# Sound_Card.net
KiCad netlist of a schematic drawn in Altium Designer
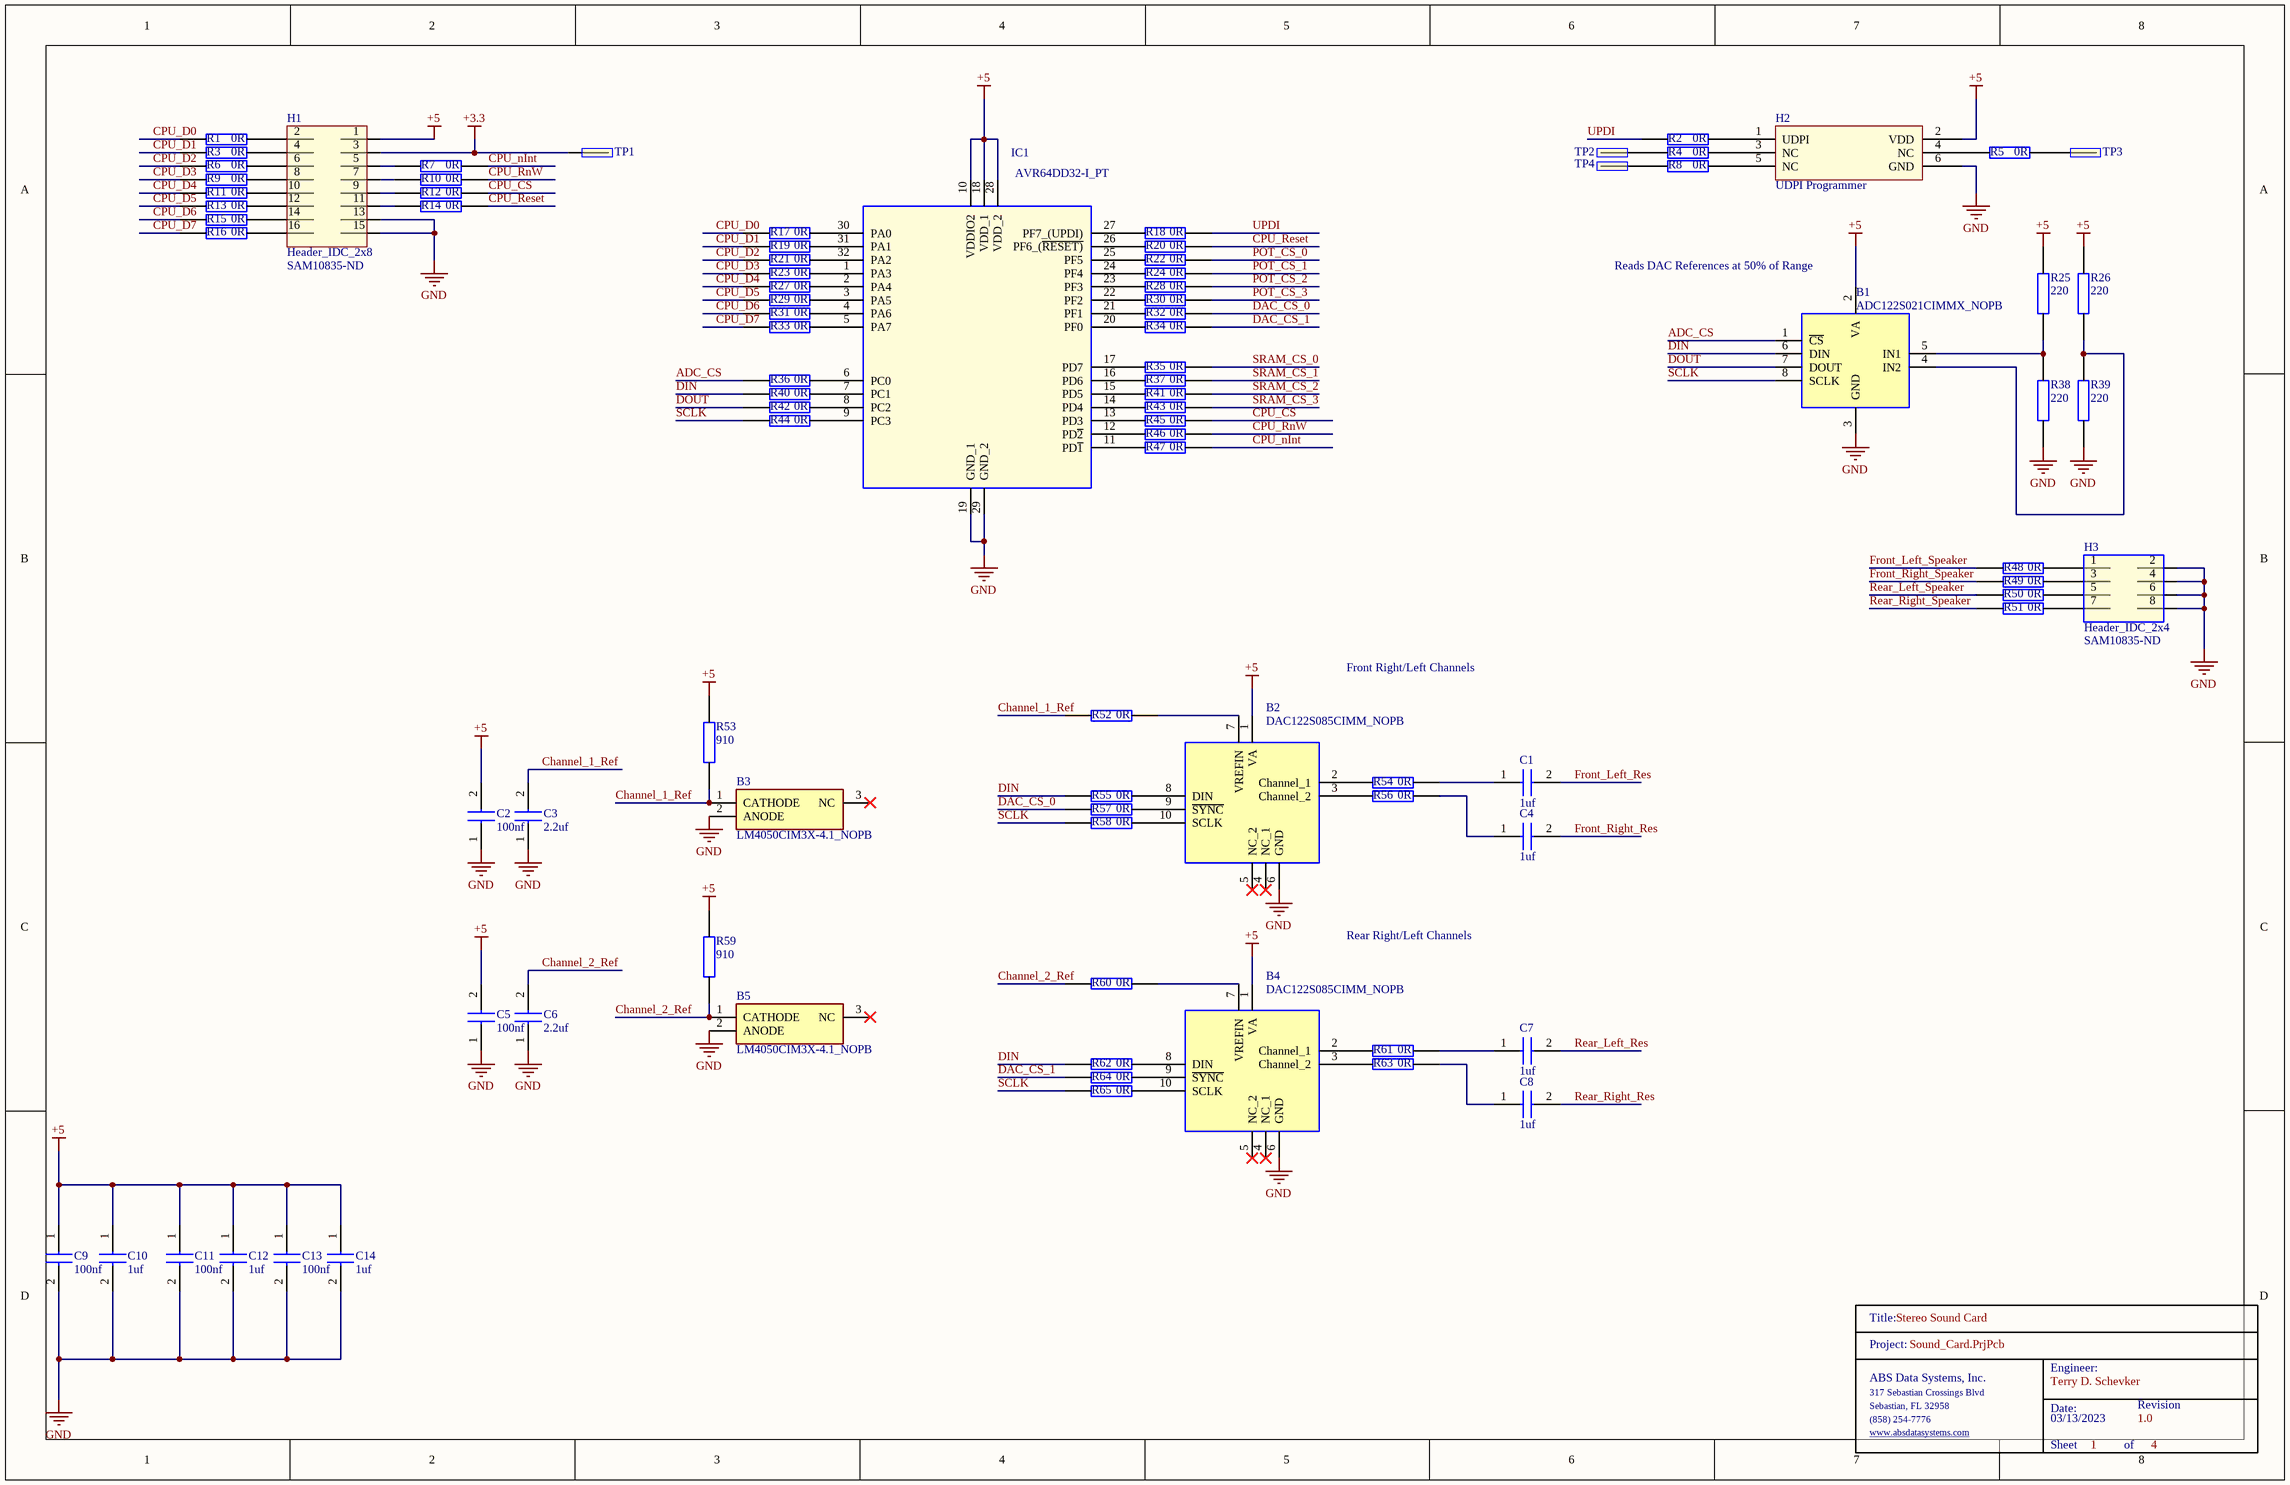
[diagram p0: Sound_Card.SchDoc]

(export (version "E")
  (design (tool "Eeschema 10.0.6"))
  (components
    (comp (ref "B1")
      (value "ADC122S021CIMMX_NOPB")
      (footprint "SOP65P490X110-8N")
      (description "2 Channel, 50 ksps to 200 ksps 12-Bit A/D Converter")
      (fields
        (field (name "MOUSER PART NUMBER") "926-A122S021CIMMXNPB")
        (field (name "MANUFACTURER_PART_NUMBER") "ADC122S021CIMMX/NOPB")
      )
      (libsource (lib "SemiConductors") (part "ADC122S021CIMMX_NOPB"))
    )
    (comp (ref "B2")
      (value "DAC122S085CIMM_NOPB")
      (footprint "SOP50P490X110-10N")
      (description "12-Bit Micro Power DUAL Digital-to-Analog Converter with Rail-to-Rail Output")
      (fields
        (field (name "MOUSER PART NUMBER") "926-DAC122S085CIMMNO")
        (field (name "MANUFACTURER_PART_NUMBER") "DAC122S085CIMM/NOPB")
      )
      (libsource (lib "SemiConductors") (part "DAC122S085CIMM_NOPB"))
    )
    (comp (ref "B3")
      (value "LM4050CIM3X-4.1_NOPB")
      (footprint "SOT95P237X95-3N")
      (description "50ppm/C Precision Micropower Shunt Voltage Reference")
      (fields
        (field (name "MOUSER PART NUMBER") "926-LM4050CIM3X41NPB")
        (field (name "MANUFACTURER_PART_NUMBER") "LM4050CIM3X-4.1/NOPB")
      )
      (libsource (lib "SemiConductors") (part "LM4050CIM3X-4.1_NOPB"))
    )
    (comp (ref "B4")
      (value "DAC122S085CIMM_NOPB")
      (footprint "SOP50P490X110-10N")
      (description "12-Bit Micro Power DUAL Digital-to-Analog Converter with Rail-to-Rail Output")
      (fields
        (field (name "MOUSER PART NUMBER") "926-DAC122S085CIMMNO")
        (field (name "MANUFACTURER_PART_NUMBER") "DAC122S085CIMM/NOPB")
      )
      (libsource (lib "SemiConductors") (part "DAC122S085CIMM_NOPB"))
    )
    (comp (ref "B5")
      (value "LM4050CIM3X-4.1_NOPB")
      (footprint "SOT95P237X95-3N")
      (description "50ppm/C Precision Micropower Shunt Voltage Reference")
      (fields
        (field (name "MOUSER PART NUMBER") "926-LM4050CIM3X41NPB")
        (field (name "MANUFACTURER_PART_NUMBER") "LM4050CIM3X-4.1/NOPB")
      )
      (libsource (lib "SemiConductors") (part "LM4050CIM3X-4.1_NOPB"))
    )
    (comp (ref "C1")
      (value "1uf")
      (footprint "0603")
      (description "Samsung Electro-Mechanics 0603 1uf")
      (libsource (lib "Capacitors") (part "CL10B105KA8NNNL"))
    )
    (comp (ref "C2")
      (value "100nf")
      (footprint "0603")
      (description "Samsung Electro-Mechanics 0603 100nf")
      (libsource (lib "Capacitors") (part "CL10B104JB8NNNC"))
    )
    (comp (ref "C3")
      (value "2.2uf")
      (footprint "0603")
      (description "Samsung Electro-Mechanics 0603 2.2uf")
      (libsource (lib "Capacitors") (part "CL10B225KP8NNNC"))
    )
    (comp (ref "C4")
      (value "1uf")
      (footprint "0603")
      (description "Samsung Electro-Mechanics 0603 1uf")
      (libsource (lib "Capacitors") (part "CL10B105KA8NNNL"))
    )
    (comp (ref "C5")
      (value "100nf")
      (footprint "0603")
      (description "Samsung Electro-Mechanics 0603 100nf")
      (libsource (lib "Capacitors") (part "CL10B104JB8NNNC"))
    )
    (comp (ref "C6")
      (value "2.2uf")
      (footprint "0603")
      (description "Samsung Electro-Mechanics 0603 2.2uf")
      (libsource (lib "Capacitors") (part "CL10B225KP8NNNC"))
    )
    (comp (ref "C7")
      (value "1uf")
      (footprint "0603")
      (description "Samsung Electro-Mechanics 0603 1uf")
      (libsource (lib "Capacitors") (part "CL10B105KA8NNNL"))
    )
    (comp (ref "C8")
      (value "1uf")
      (footprint "0603")
      (description "Samsung Electro-Mechanics 0603 1uf")
      (libsource (lib "Capacitors") (part "CL10B105KA8NNNL"))
    )
    (comp (ref "C9")
      (value "100nf")
      (footprint "0603")
      (description "Samsung Electro-Mechanics 0603 100nf")
      (libsource (lib "Capacitors") (part "CL10B104JB8NNNC"))
    )
    (comp (ref "C10")
      (value "1uf")
      (footprint "0603")
      (description "Samsung Electro-Mechanics 0603 1uf")
      (libsource (lib "Capacitors") (part "CL10B105KA8NNNL"))
    )
    (comp (ref "C11")
      (value "100nf")
      (footprint "0603")
      (description "Samsung Electro-Mechanics 0603 100nf")
      (libsource (lib "Capacitors") (part "CL10B104JB8NNNC"))
    )
    (comp (ref "C12")
      (value "1uf")
      (footprint "0603")
      (description "Samsung Electro-Mechanics 0603 1uf")
      (libsource (lib "Capacitors") (part "CL10B105KA8NNNL"))
    )
    (comp (ref "C13")
      (value "100nf")
      (footprint "0603")
      (description "Samsung Electro-Mechanics 0603 100nf")
      (libsource (lib "Capacitors") (part "CL10B104JB8NNNC"))
    )
    (comp (ref "C14")
      (value "1uf")
      (footprint "0603")
      (description "Samsung Electro-Mechanics 0603 1uf")
      (libsource (lib "Capacitors") (part "CL10B105KA8NNNL"))
    )
    (comp (ref "H1")
      (value "Header_IDC_2x8")
      (footprint "HEADER16")
      (description "16 Pin 2x8 Through Hold IDC Connector")
      (fields
        (field (name "MANUFACTURER") "Samtec")
        (field (name "MANUFACTURER PART NUMBER") "TST-108-01-G-D")
        (field (name "SUPPLIER PART NUMBER 1") "SAM10835-ND")
      )
      (libsource (lib "Misc") (part "Header_IDC_2x8"))
    )
    (comp (ref "H2")
      (value "UDPI Programmer")
      (footprint "HDR2X3")
      (description "6 Pin 2X3 Through Hole Header")
      (libsource (lib "Misc") (part "UDPI Programmer"))
    )
    (comp (ref "H3")
      (value "Header_IDC_2x4")
      (footprint "HDR2X4")
      (description "8 Pin 2x4 Through Hold IDC Connector")
      (fields
        (field (name "MANUFACTURER") "Samtec")
        (field (name "MANUFACTURER PART NUMBER") "TST-105-01-G-D")
        (field (name "SUPPLIER PART NUMBER 1") "SAM10835-ND")
      )
      (libsource (lib "Misc") (part "Header_IDC_2x4"))
    )
    (comp (ref "IC1")
      (value "AVR64DD32-I_PT")
      (footprint "QFP80P900X900X120-32N")
      (description "Integrated Circuit")
      (fields (field (name "MANUFACTURER_PART_NUMBER") "AVR64DD32-I/PT ¦ MULTI-VOLTAGE I/O"))
      (libsource (lib "CPU_Memory") (part "AVR64DD32-I_PT"))
    )
    (comp (ref "R1")
      (value "0R")
      (footprint "0603")
      (description "YAGEO 0603 0 ohm")
      (fields
        (field (name "MOUSER PART NUMBER") "603-RC0603JR-070RL")
        (field (name "MANUFACTURER_PART_NUMBER") "RC0603JR-070RL")
      )
      (libsource (lib "Resistors") (part "RC0603JR-070RL"))
    )
    (comp (ref "R2")
      (value "0R")
      (footprint "0603")
      (description "YAGEO 0603 0 ohm")
      (fields
        (field (name "MOUSER PART NUMBER") "603-RC0603JR-070RL")
        (field (name "MANUFACTURER_PART_NUMBER") "RC0603JR-070RL")
      )
      (libsource (lib "Resistors") (part "RC0603JR-070RL"))
    )
    (comp (ref "R3")
      (value "0R")
      (footprint "0603")
      (description "YAGEO 0603 0 ohm")
      (fields
        (field (name "MOUSER PART NUMBER") "603-RC0603JR-070RL")
        (field (name "MANUFACTURER_PART_NUMBER") "RC0603JR-070RL")
      )
      (libsource (lib "Resistors") (part "RC0603JR-070RL"))
    )
    (comp (ref "R4")
      (value "0R")
      (footprint "0603")
      (description "YAGEO 0603 0 ohm")
      (fields
        (field (name "MOUSER PART NUMBER") "603-RC0603JR-070RL")
        (field (name "MANUFACTURER_PART_NUMBER") "RC0603JR-070RL")
      )
      (libsource (lib "Resistors") (part "RC0603JR-070RL"))
    )
    (comp (ref "R5")
      (value "0R")
      (footprint "0603")
      (description "YAGEO 0603 0 ohm")
      (fields
        (field (name "MOUSER PART NUMBER") "603-RC0603JR-070RL")
        (field (name "MANUFACTURER_PART_NUMBER") "RC0603JR-070RL")
      )
      (libsource (lib "Resistors") (part "RC0603JR-070RL"))
    )
    (comp (ref "R6")
      (value "0R")
      (footprint "0603")
      (description "YAGEO 0603 0 ohm")
      (fields
        (field (name "MOUSER PART NUMBER") "603-RC0603JR-070RL")
        (field (name "MANUFACTURER_PART_NUMBER") "RC0603JR-070RL")
      )
      (libsource (lib "Resistors") (part "RC0603JR-070RL"))
    )
    (comp (ref "R7")
      (value "0R")
      (footprint "0603")
      (description "YAGEO 0603 0 ohm")
      (fields
        (field (name "MOUSER PART NUMBER") "603-RC0603JR-070RL")
        (field (name "MANUFACTURER_PART_NUMBER") "RC0603JR-070RL")
      )
      (libsource (lib "Resistors") (part "RC0603JR-070RL"))
    )
    (comp (ref "R8")
      (value "0R")
      (footprint "0603")
      (description "YAGEO 0603 0 ohm")
      (fields
        (field (name "MOUSER PART NUMBER") "603-RC0603JR-070RL")
        (field (name "MANUFACTURER_PART_NUMBER") "RC0603JR-070RL")
      )
      (libsource (lib "Resistors") (part "RC0603JR-070RL"))
    )
    (comp (ref "R9")
      (value "0R")
      (footprint "0603")
      (description "YAGEO 0603 0 ohm")
      (fields
        (field (name "MOUSER PART NUMBER") "603-RC0603JR-070RL")
        (field (name "MANUFACTURER_PART_NUMBER") "RC0603JR-070RL")
      )
      (libsource (lib "Resistors") (part "RC0603JR-070RL"))
    )
    (comp (ref "R10")
      (value "0R")
      (footprint "0603")
      (description "YAGEO 0603 0 ohm")
      (fields
        (field (name "MOUSER PART NUMBER") "603-RC0603JR-070RL")
        (field (name "MANUFACTURER_PART_NUMBER") "RC0603JR-070RL")
      )
      (libsource (lib "Resistors") (part "RC0603JR-070RL"))
    )
    (comp (ref "R11")
      (value "0R")
      (footprint "0603")
      (description "YAGEO 0603 0 ohm")
      (fields
        (field (name "MOUSER PART NUMBER") "603-RC0603JR-070RL")
        (field (name "MANUFACTURER_PART_NUMBER") "RC0603JR-070RL")
      )
      (libsource (lib "Resistors") (part "RC0603JR-070RL"))
    )
    (comp (ref "R12")
      (value "0R")
      (footprint "0603")
      (description "YAGEO 0603 0 ohm")
      (fields
        (field (name "MOUSER PART NUMBER") "603-RC0603JR-070RL")
        (field (name "MANUFACTURER_PART_NUMBER") "RC0603JR-070RL")
      )
      (libsource (lib "Resistors") (part "RC0603JR-070RL"))
    )
    (comp (ref "R13")
      (value "0R")
      (footprint "0603")
      (description "YAGEO 0603 0 ohm")
      (fields
        (field (name "MOUSER PART NUMBER") "603-RC0603JR-070RL")
        (field (name "MANUFACTURER_PART_NUMBER") "RC0603JR-070RL")
      )
      (libsource (lib "Resistors") (part "RC0603JR-070RL"))
    )
    (comp (ref "R14")
      (value "0R")
      (footprint "0603")
      (description "YAGEO 0603 0 ohm")
      (fields
        (field (name "MOUSER PART NUMBER") "603-RC0603JR-070RL")
        (field (name "MANUFACTURER_PART_NUMBER") "RC0603JR-070RL")
      )
      (libsource (lib "Resistors") (part "RC0603JR-070RL"))
    )
    (comp (ref "R15")
      (value "0R")
      (footprint "0603")
      (description "YAGEO 0603 0 ohm")
      (fields
        (field (name "MOUSER PART NUMBER") "603-RC0603JR-070RL")
        (field (name "MANUFACTURER_PART_NUMBER") "RC0603JR-070RL")
      )
      (libsource (lib "Resistors") (part "RC0603JR-070RL"))
    )
    (comp (ref "R16")
      (value "0R")
      (footprint "0603")
      (description "YAGEO 0603 0 ohm")
      (fields
        (field (name "MOUSER PART NUMBER") "603-RC0603JR-070RL")
        (field (name "MANUFACTURER_PART_NUMBER") "RC0603JR-070RL")
      )
      (libsource (lib "Resistors") (part "RC0603JR-070RL"))
    )
    (comp (ref "R17")
      (value "0R")
      (footprint "0603")
      (description "YAGEO 0603 0 ohm")
      (fields
        (field (name "MOUSER PART NUMBER") "603-RC0603JR-070RL")
        (field (name "MANUFACTURER_PART_NUMBER") "RC0603JR-070RL")
      )
      (libsource (lib "Resistors") (part "RC0603JR-070RL"))
    )
    (comp (ref "R18")
      (value "0R")
      (footprint "0603")
      (description "YAGEO 0603 0 ohm")
      (fields
        (field (name "MOUSER PART NUMBER") "603-RC0603JR-070RL")
        (field (name "MANUFACTURER_PART_NUMBER") "RC0603JR-070RL")
      )
      (libsource (lib "Resistors") (part "RC0603JR-070RL"))
    )
    (comp (ref "R19")
      (value "0R")
      (footprint "0603")
      (description "YAGEO 0603 0 ohm")
      (fields
        (field (name "MOUSER PART NUMBER") "603-RC0603JR-070RL")
        (field (name "MANUFACTURER_PART_NUMBER") "RC0603JR-070RL")
      )
      (libsource (lib "Resistors") (part "RC0603JR-070RL"))
    )
    (comp (ref "R20")
      (value "0R")
      (footprint "0603")
      (description "YAGEO 0603 0 ohm")
      (fields
        (field (name "MOUSER PART NUMBER") "603-RC0603JR-070RL")
        (field (name "MANUFACTURER_PART_NUMBER") "RC0603JR-070RL")
      )
      (libsource (lib "Resistors") (part "RC0603JR-070RL"))
    )
    (comp (ref "R21")
      (value "0R")
      (footprint "0603")
      (description "YAGEO 0603 0 ohm")
      (fields
        (field (name "MOUSER PART NUMBER") "603-RC0603JR-070RL")
        (field (name "MANUFACTURER_PART_NUMBER") "RC0603JR-070RL")
      )
      (libsource (lib "Resistors") (part "RC0603JR-070RL"))
    )
    (comp (ref "R22")
      (value "0R")
      (footprint "0603")
      (description "YAGEO 0603 0 ohm")
      (fields
        (field (name "MOUSER PART NUMBER") "603-RC0603JR-070RL")
        (field (name "MANUFACTURER_PART_NUMBER") "RC0603JR-070RL")
      )
      (libsource (lib "Resistors") (part "RC0603JR-070RL"))
    )
    (comp (ref "R23")
      (value "0R")
      (footprint "0603")
      (description "YAGEO 0603 0 ohm")
      (fields
        (field (name "MOUSER PART NUMBER") "603-RC0603JR-070RL")
        (field (name "MANUFACTURER_PART_NUMBER") "RC0603JR-070RL")
      )
      (libsource (lib "Resistors") (part "RC0603JR-070RL"))
    )
    (comp (ref "R24")
      (value "0R")
      (footprint "0603")
      (description "YAGEO 0603 0 ohm")
      (fields
        (field (name "MOUSER PART NUMBER") "603-RC0603JR-070RL")
        (field (name "MANUFACTURER_PART_NUMBER") "RC0603JR-070RL")
      )
      (libsource (lib "Resistors") (part "RC0603JR-070RL"))
    )
    (comp (ref "R25")
      (value "220")
      (footprint "0603")
      (description "YAGEO 0603 220 ohm")
      (fields
        (field (name "MOUSER PART NUMBER") "603-RC0603JR-070RL")
        (field (name "MANUFACTURER_PART_NUMBER") "RC0603JR-070RL")
      )
      (libsource (lib "Resistors") (part "RC0603JR-07220RL"))
    )
    (comp (ref "R26")
      (value "220")
      (footprint "0603")
      (description "YAGEO 0603 220 ohm")
      (fields
        (field (name "MOUSER PART NUMBER") "603-RC0603JR-070RL")
        (field (name "MANUFACTURER_PART_NUMBER") "RC0603JR-070RL")
      )
      (libsource (lib "Resistors") (part "RC0603JR-07220RL"))
    )
    (comp (ref "R27")
      (value "0R")
      (footprint "0603")
      (description "YAGEO 0603 0 ohm")
      (fields
        (field (name "MOUSER PART NUMBER") "603-RC0603JR-070RL")
        (field (name "MANUFACTURER_PART_NUMBER") "RC0603JR-070RL")
      )
      (libsource (lib "Resistors") (part "RC0603JR-070RL"))
    )
    (comp (ref "R28")
      (value "0R")
      (footprint "0603")
      (description "YAGEO 0603 0 ohm")
      (fields
        (field (name "MOUSER PART NUMBER") "603-RC0603JR-070RL")
        (field (name "MANUFACTURER_PART_NUMBER") "RC0603JR-070RL")
      )
      (libsource (lib "Resistors") (part "RC0603JR-070RL"))
    )
    (comp (ref "R29")
      (value "0R")
      (footprint "0603")
      (description "YAGEO 0603 0 ohm")
      (fields
        (field (name "MOUSER PART NUMBER") "603-RC0603JR-070RL")
        (field (name "MANUFACTURER_PART_NUMBER") "RC0603JR-070RL")
      )
      (libsource (lib "Resistors") (part "RC0603JR-070RL"))
    )
    (comp (ref "R30")
      (value "0R")
      (footprint "0603")
      (description "YAGEO 0603 0 ohm")
      (fields
        (field (name "MOUSER PART NUMBER") "603-RC0603JR-070RL")
        (field (name "MANUFACTURER_PART_NUMBER") "RC0603JR-070RL")
      )
      (libsource (lib "Resistors") (part "RC0603JR-070RL"))
    )
    (comp (ref "R31")
      (value "0R")
      (footprint "0603")
      (description "YAGEO 0603 0 ohm")
      (fields
        (field (name "MOUSER PART NUMBER") "603-RC0603JR-070RL")
        (field (name "MANUFACTURER_PART_NUMBER") "RC0603JR-070RL")
      )
      (libsource (lib "Resistors") (part "RC0603JR-070RL"))
    )
    (comp (ref "R32")
      (value "0R")
      (footprint "0603")
      (description "YAGEO 0603 0 ohm")
      (fields
        (field (name "MOUSER PART NUMBER") "603-RC0603JR-070RL")
        (field (name "MANUFACTURER_PART_NUMBER") "RC0603JR-070RL")
      )
      (libsource (lib "Resistors") (part "RC0603JR-070RL"))
    )
    (comp (ref "R33")
      (value "0R")
      (footprint "0603")
      (description "YAGEO 0603 0 ohm")
      (fields
        (field (name "MOUSER PART NUMBER") "603-RC0603JR-070RL")
        (field (name "MANUFACTURER_PART_NUMBER") "RC0603JR-070RL")
      )
      (libsource (lib "Resistors") (part "RC0603JR-070RL"))
    )
    (comp (ref "R34")
      (value "0R")
      (footprint "0603")
      (description "YAGEO 0603 0 ohm")
      (fields
        (field (name "MOUSER PART NUMBER") "603-RC0603JR-070RL")
        (field (name "MANUFACTURER_PART_NUMBER") "RC0603JR-070RL")
      )
      (libsource (lib "Resistors") (part "RC0603JR-070RL"))
    )
    (comp (ref "R35")
      (value "0R")
      (footprint "0603")
      (description "YAGEO 0603 0 ohm")
      (fields
        (field (name "MOUSER PART NUMBER") "603-RC0603JR-070RL")
        (field (name "MANUFACTURER_PART_NUMBER") "RC0603JR-070RL")
      )
      (libsource (lib "Resistors") (part "RC0603JR-070RL"))
    )
    (comp (ref "R36")
      (value "0R")
      (footprint "0603")
      (description "YAGEO 0603 0 ohm")
      (fields
        (field (name "MOUSER PART NUMBER") "603-RC0603JR-070RL")
        (field (name "MANUFACTURER_PART_NUMBER") "RC0603JR-070RL")
      )
      (libsource (lib "Resistors") (part "RC0603JR-070RL"))
    )
    (comp (ref "R37")
      (value "0R")
      (footprint "0603")
      (description "YAGEO 0603 0 ohm")
      (fields
        (field (name "MOUSER PART NUMBER") "603-RC0603JR-070RL")
        (field (name "MANUFACTURER_PART_NUMBER") "RC0603JR-070RL")
      )
      (libsource (lib "Resistors") (part "RC0603JR-070RL"))
    )
    (comp (ref "R38")
      (value "220")
      (footprint "0603")
      (description "YAGEO 0603 220 ohm")
      (fields
        (field (name "MOUSER PART NUMBER") "603-RC0603JR-070RL")
        (field (name "MANUFACTURER_PART_NUMBER") "RC0603JR-070RL")
      )
      (libsource (lib "Resistors") (part "RC0603JR-07220RL"))
    )
    (comp (ref "R39")
      (value "220")
      (footprint "0603")
      (description "YAGEO 0603 220 ohm")
      (fields
        (field (name "MOUSER PART NUMBER") "603-RC0603JR-070RL")
        (field (name "MANUFACTURER_PART_NUMBER") "RC0603JR-070RL")
      )
      (libsource (lib "Resistors") (part "RC0603JR-07220RL"))
    )
    (comp (ref "R40")
      (value "0R")
      (footprint "0603")
      (description "YAGEO 0603 0 ohm")
      (fields
        (field (name "MOUSER PART NUMBER") "603-RC0603JR-070RL")
        (field (name "MANUFACTURER_PART_NUMBER") "RC0603JR-070RL")
      )
      (libsource (lib "Resistors") (part "RC0603JR-070RL"))
    )
    (comp (ref "R41")
      (value "0R")
      (footprint "0603")
      (description "YAGEO 0603 0 ohm")
      (fields
        (field (name "MOUSER PART NUMBER") "603-RC0603JR-070RL")
        (field (name "MANUFACTURER_PART_NUMBER") "RC0603JR-070RL")
      )
      (libsource (lib "Resistors") (part "RC0603JR-070RL"))
    )
    (comp (ref "R42")
      (value "0R")
      (footprint "0603")
      (description "YAGEO 0603 0 ohm")
      (fields
        (field (name "MOUSER PART NUMBER") "603-RC0603JR-070RL")
        (field (name "MANUFACTURER_PART_NUMBER") "RC0603JR-070RL")
      )
      (libsource (lib "Resistors") (part "RC0603JR-070RL"))
    )
    (comp (ref "R43")
      (value "0R")
      (footprint "0603")
      (description "YAGEO 0603 0 ohm")
      (fields
        (field (name "MOUSER PART NUMBER") "603-RC0603JR-070RL")
        (field (name "MANUFACTURER_PART_NUMBER") "RC0603JR-070RL")
      )
      (libsource (lib "Resistors") (part "RC0603JR-070RL"))
    )
    (comp (ref "R44")
      (value "0R")
      (footprint "0603")
      (description "YAGEO 0603 0 ohm")
      (fields
        (field (name "MOUSER PART NUMBER") "603-RC0603JR-070RL")
        (field (name "MANUFACTURER_PART_NUMBER") "RC0603JR-070RL")
      )
      (libsource (lib "Resistors") (part "RC0603JR-070RL"))
    )
    (comp (ref "R45")
      (value "0R")
      (footprint "0603")
      (description "YAGEO 0603 0 ohm")
      (fields
        (field (name "MOUSER PART NUMBER") "603-RC0603JR-070RL")
        (field (name "MANUFACTURER_PART_NUMBER") "RC0603JR-070RL")
      )
      (libsource (lib "Resistors") (part "RC0603JR-070RL"))
    )
    (comp (ref "R46")
      (value "0R")
      (footprint "0603")
      (description "YAGEO 0603 0 ohm")
      (fields
        (field (name "MOUSER PART NUMBER") "603-RC0603JR-070RL")
        (field (name "MANUFACTURER_PART_NUMBER") "RC0603JR-070RL")
      )
      (libsource (lib "Resistors") (part "RC0603JR-070RL"))
    )
    (comp (ref "R47")
      (value "0R")
      (footprint "0603")
      (description "YAGEO 0603 0 ohm")
      (fields
        (field (name "MOUSER PART NUMBER") "603-RC0603JR-070RL")
        (field (name "MANUFACTURER_PART_NUMBER") "RC0603JR-070RL")
      )
      (libsource (lib "Resistors") (part "RC0603JR-070RL"))
    )
    (comp (ref "R48")
      (value "0R")
      (footprint "0603")
      (description "YAGEO 0603 0 ohm")
      (fields
        (field (name "MOUSER PART NUMBER") "603-RC0603JR-070RL")
        (field (name "MANUFACTURER_PART_NUMBER") "RC0603JR-070RL")
      )
      (libsource (lib "Resistors") (part "RC0603JR-070RL"))
    )
    (comp (ref "R49")
      (value "0R")
      (footprint "0603")
      (description "YAGEO 0603 0 ohm")
      (fields
        (field (name "MOUSER PART NUMBER") "603-RC0603JR-070RL")
        (field (name "MANUFACTURER_PART_NUMBER") "RC0603JR-070RL")
      )
      (libsource (lib "Resistors") (part "RC0603JR-070RL"))
    )
    (comp (ref "R50")
      (value "0R")
      (footprint "0603")
      (description "YAGEO 0603 0 ohm")
      (fields
        (field (name "MOUSER PART NUMBER") "603-RC0603JR-070RL")
        (field (name "MANUFACTURER_PART_NUMBER") "RC0603JR-070RL")
      )
      (libsource (lib "Resistors") (part "RC0603JR-070RL"))
    )
    (comp (ref "R51")
      (value "0R")
      (footprint "0603")
      (description "YAGEO 0603 0 ohm")
      (fields
        (field (name "MOUSER PART NUMBER") "603-RC0603JR-070RL")
        (field (name "MANUFACTURER_PART_NUMBER") "RC0603JR-070RL")
      )
      (libsource (lib "Resistors") (part "RC0603JR-070RL"))
    )
    (comp (ref "R52")
      (value "0R")
      (footprint "0603")
      (description "YAGEO 0603 0 ohm")
      (fields
        (field (name "MOUSER PART NUMBER") "603-RC0603JR-070RL")
        (field (name "MANUFACTURER_PART_NUMBER") "RC0603JR-070RL")
      )
      (libsource (lib "Resistors") (part "RC0603JR-070RL"))
    )
    (comp (ref "R53")
      (value "910")
      (footprint "0603")
      (description "YAGEO 0603 910 ohm")
      (fields
        (field (name "MOUSER PART NUMBER") "603-RC0603JR-070RL")
        (field (name "MANUFACTURER_PART_NUMBER") "RC0603JR-070RL")
      )
      (libsource (lib "Resistors") (part "RT0603BRC07910RL"))
    )
    (comp (ref "R54")
      (value "0R")
      (footprint "0603")
      (description "YAGEO 0603 0 ohm")
      (fields
        (field (name "MOUSER PART NUMBER") "603-RC0603JR-070RL")
        (field (name "MANUFACTURER_PART_NUMBER") "RC0603JR-070RL")
      )
      (libsource (lib "Resistors") (part "RC0603JR-070RL"))
    )
    (comp (ref "R55")
      (value "0R")
      (footprint "0603")
      (description "YAGEO 0603 0 ohm")
      (fields
        (field (name "MOUSER PART NUMBER") "603-RC0603JR-070RL")
        (field (name "MANUFACTURER_PART_NUMBER") "RC0603JR-070RL")
      )
      (libsource (lib "Resistors") (part "RC0603JR-070RL"))
    )
    (comp (ref "R56")
      (value "0R")
      (footprint "0603")
      (description "YAGEO 0603 0 ohm")
      (fields
        (field (name "MOUSER PART NUMBER") "603-RC0603JR-070RL")
        (field (name "MANUFACTURER_PART_NUMBER") "RC0603JR-070RL")
      )
      (libsource (lib "Resistors") (part "RC0603JR-070RL"))
    )
    (comp (ref "R57")
      (value "0R")
      (footprint "0603")
      (description "YAGEO 0603 0 ohm")
      (fields
        (field (name "MOUSER PART NUMBER") "603-RC0603JR-070RL")
        (field (name "MANUFACTURER_PART_NUMBER") "RC0603JR-070RL")
      )
      (libsource (lib "Resistors") (part "RC0603JR-070RL"))
    )
    (comp (ref "R58")
      (value "0R")
      (footprint "0603")
      (description "YAGEO 0603 0 ohm")
      (fields
        (field (name "MOUSER PART NUMBER") "603-RC0603JR-070RL")
        (field (name "MANUFACTURER_PART_NUMBER") "RC0603JR-070RL")
      )
      (libsource (lib "Resistors") (part "RC0603JR-070RL"))
    )
    (comp (ref "R59")
      (value "910")
      (footprint "0603")
      (description "YAGEO 0603 910 ohm")
      (fields
        (field (name "MOUSER PART NUMBER") "603-RC0603JR-070RL")
        (field (name "MANUFACTURER_PART_NUMBER") "RC0603JR-070RL")
      )
      (libsource (lib "Resistors") (part "RT0603BRC07910RL"))
    )
    (comp (ref "R60")
      (value "0R")
      (footprint "0603")
      (description "YAGEO 0603 0 ohm")
      (fields
        (field (name "MOUSER PART NUMBER") "603-RC0603JR-070RL")
        (field (name "MANUFACTURER_PART_NUMBER") "RC0603JR-070RL")
      )
      (libsource (lib "Resistors") (part "RC0603JR-070RL"))
    )
    (comp (ref "R61")
      (value "0R")
      (footprint "0603")
      (description "YAGEO 0603 0 ohm")
      (fields
        (field (name "MOUSER PART NUMBER") "603-RC0603JR-070RL")
        (field (name "MANUFACTURER_PART_NUMBER") "RC0603JR-070RL")
      )
      (libsource (lib "Resistors") (part "RC0603JR-070RL"))
    )
    (comp (ref "R62")
      (value "0R")
      (footprint "0603")
      (description "YAGEO 0603 0 ohm")
      (fields
        (field (name "MOUSER PART NUMBER") "603-RC0603JR-070RL")
        (field (name "MANUFACTURER_PART_NUMBER") "RC0603JR-070RL")
      )
      (libsource (lib "Resistors") (part "RC0603JR-070RL"))
    )
    (comp (ref "R63")
      (value "0R")
      (footprint "0603")
      (description "YAGEO 0603 0 ohm")
      (fields
        (field (name "MOUSER PART NUMBER") "603-RC0603JR-070RL")
        (field (name "MANUFACTURER_PART_NUMBER") "RC0603JR-070RL")
      )
      (libsource (lib "Resistors") (part "RC0603JR-070RL"))
    )
    (comp (ref "R64")
      (value "0R")
      (footprint "0603")
      (description "YAGEO 0603 0 ohm")
      (fields
        (field (name "MOUSER PART NUMBER") "603-RC0603JR-070RL")
        (field (name "MANUFACTURER_PART_NUMBER") "RC0603JR-070RL")
      )
      (libsource (lib "Resistors") (part "RC0603JR-070RL"))
    )
    (comp (ref "R65")
      (value "0R")
      (footprint "0603")
      (description "YAGEO 0603 0 ohm")
      (fields
        (field (name "MOUSER PART NUMBER") "603-RC0603JR-070RL")
        (field (name "MANUFACTURER_PART_NUMBER") "RC0603JR-070RL")
      )
      (libsource (lib "Resistors") (part "RC0603JR-070RL"))
    )
    (comp (ref "TitleBlock_1") (value "TitleBlock") (libsource (lib "Misc") (part "TitleBlock")))
    (comp (ref "TP1")
      (value "TP")
      (footprint "TP")
      (fields
        (field (name "MANUFACTURER") "Samtec")
        (field (name "MANUFACTURER PART NUMBER") "TST-105-01-G-D")
      )
      (libsource (lib "") (part "TP_1"))
    )
    (comp (ref "TP2")
      (value "TP")
      (footprint "TP")
      (fields
        (field (name "MANUFACTURER") "Samtec")
        (field (name "MANUFACTURER PART NUMBER") "TST-105-01-G-D")
      )
      (libsource (lib "Misc") (part "TP"))
    )
    (comp (ref "TP3")
      (value "TP")
      (footprint "TP")
      (fields
        (field (name "MANUFACTURER") "Samtec")
        (field (name "MANUFACTURER PART NUMBER") "TST-105-01-G-D")
      )
      (libsource (lib "") (part "TP_1"))
    )
    (comp (ref "TP4")
      (value "TP")
      (footprint "TP")
      (fields
        (field (name "MANUFACTURER") "Samtec")
        (field (name "MANUFACTURER PART NUMBER") "TST-105-01-G-D")
      )
      (libsource (lib "Misc") (part "TP"))
    )
  )
  (nets
    (net (code "1") (name "+3.3") (class "Default")
      (node (ref "H1") (pin "3") (pinfunction "3_3") (pintype "passive"))
      (node (ref "TP1") (pin "1") (pinfunction "1_1") (pintype "passive"))
    )
    (net (code "2") (name "+5") (class "Default")
      (node (ref "B1") (pin "2") (pinfunction "VA_2") (pintype "passive"))
      (node (ref "B2") (pin "1") (pinfunction "VA_1") (pintype "passive"))
      (node (ref "B4") (pin "1") (pinfunction "VA_1") (pintype "passive"))
      (node (ref "C10") (pin "1") (pinfunction "1_1") (pintype "passive"))
      (node (ref "C11") (pin "1") (pinfunction "1_1") (pintype "passive"))
      (node (ref "C12") (pin "1") (pinfunction "1_1") (pintype "passive"))
      (node (ref "C13") (pin "1") (pinfunction "1_1") (pintype "passive"))
      (node (ref "C14") (pin "1") (pinfunction "1_1") (pintype "passive"))
      (node (ref "C2") (pin "2") (pinfunction "2_2") (pintype "passive"))
      (node (ref "C5") (pin "2") (pinfunction "2_2") (pintype "passive"))
      (node (ref "C9") (pin "1") (pinfunction "1_1") (pintype "passive"))
      (node (ref "H1") (pin "1") (pinfunction "1_1") (pintype "passive"))
      (node (ref "H2") (pin "2") (pinfunction "VDD_2") (pintype "passive"))
      (node (ref "IC1") (pin "10") (pinfunction "VDDIO2_10") (pintype "passive"))
      (node (ref "IC1") (pin "18") (pinfunction "VDD_1_18") (pintype "passive"))
      (node (ref "IC1") (pin "28") (pinfunction "VDD_2_28") (pintype "passive"))
      (node (ref "R25") (pin "1") (pinfunction "1_1") (pintype "passive"))
      (node (ref "R26") (pin "2") (pinfunction "2_2") (pintype "passive"))
      (node (ref "R53") (pin "1") (pinfunction "1_1") (pintype "passive"))
      (node (ref "R59") (pin "1") (pinfunction "1_1") (pintype "passive"))
    )
    (net (code "3") (name "/ADC_CS") (class "Default")
      (node (ref "B1") (pin "1") (pinfunction "~{CS}_1") (pintype "passive"))
      (node (ref "R36") (pin "1") (pinfunction "1_1") (pintype "passive"))
    )
    (net (code "4") (name "/CPU_CS") (class "Default")
      (node (ref "R12") (pin "2") (pinfunction "2_2") (pintype "passive"))
      (node (ref "R45") (pin "2") (pinfunction "2_2") (pintype "passive"))
    )
    (net (code "5") (name "/CPU_D0") (class "Default")
      (node (ref "R1") (pin "1") (pinfunction "1_1") (pintype "passive"))
      (node (ref "R17") (pin "1") (pinfunction "1_1") (pintype "passive"))
    )
    (net (code "6") (name "/CPU_D1") (class "Default")
      (node (ref "R19") (pin "1") (pinfunction "1_1") (pintype "passive"))
      (node (ref "R3") (pin "1") (pinfunction "1_1") (pintype "passive"))
    )
    (net (code "7") (name "/CPU_D2") (class "Default")
      (node (ref "R21") (pin "1") (pinfunction "1_1") (pintype "passive"))
      (node (ref "R6") (pin "1") (pinfunction "1_1") (pintype "passive"))
    )
    (net (code "8") (name "/CPU_D3") (class "Default")
      (node (ref "R23") (pin "1") (pinfunction "1_1") (pintype "passive"))
      (node (ref "R9") (pin "1") (pinfunction "1_1") (pintype "passive"))
    )
    (net (code "9") (name "/CPU_D4") (class "Default")
      (node (ref "R11") (pin "1") (pinfunction "1_1") (pintype "passive"))
      (node (ref "R27") (pin "1") (pinfunction "1_1") (pintype "passive"))
    )
    (net (code "10") (name "/CPU_D5") (class "Default")
      (node (ref "R13") (pin "1") (pinfunction "1_1") (pintype "passive"))
      (node (ref "R29") (pin "1") (pinfunction "1_1") (pintype "passive"))
    )
    (net (code "11") (name "/CPU_D6") (class "Default")
      (node (ref "R15") (pin "1") (pinfunction "1_1") (pintype "passive"))
      (node (ref "R31") (pin "1") (pinfunction "1_1") (pintype "passive"))
    )
    (net (code "12") (name "/CPU_D7") (class "Default")
      (node (ref "R16") (pin "1") (pinfunction "1_1") (pintype "passive"))
      (node (ref "R33") (pin "1") (pinfunction "1_1") (pintype "passive"))
    )
    (net (code "13") (name "/CPU_Reset") (class "Default")
      (node (ref "R14") (pin "2") (pinfunction "2_2") (pintype "passive"))
      (node (ref "R20") (pin "2") (pinfunction "2_2") (pintype "passive"))
    )
    (net (code "14") (name "/CPU_RnW") (class "Default")
      (node (ref "R10") (pin "2") (pinfunction "2_2") (pintype "passive"))
      (node (ref "R46") (pin "2") (pinfunction "2_2") (pintype "passive"))
    )
    (net (code "15") (name "/CPU_nInt") (class "Default")
      (node (ref "R47") (pin "2") (pinfunction "2_2") (pintype "passive"))
      (node (ref "R7") (pin "2") (pinfunction "2_2") (pintype "passive"))
    )
    (net (code "16") (name "/Channel_1_Ref") (class "Default")
      (node (ref "B3") (pin "1") (pinfunction "CATHODE_1") (pintype "passive"))
      (node (ref "C3") (pin "2") (pinfunction "2_2") (pintype "passive"))
      (node (ref "R52") (pin "1") (pinfunction "1_1") (pintype "passive"))
      (node (ref "R53") (pin "2") (pinfunction "2_2") (pintype "passive"))
    )
    (net (code "17") (name "/Channel_2_Ref") (class "Default")
      (node (ref "B5") (pin "1") (pinfunction "CATHODE_1") (pintype "passive"))
      (node (ref "C6") (pin "2") (pinfunction "2_2") (pintype "passive"))
      (node (ref "R59") (pin "2") (pinfunction "2_2") (pintype "passive"))
      (node (ref "R60") (pin "1") (pinfunction "1_1") (pintype "passive"))
    )
    (net (code "18") (name "/DAC_CS_0") (class "Default")
      (node (ref "R32") (pin "2") (pinfunction "2_2") (pintype "passive"))
      (node (ref "R57") (pin "1") (pinfunction "1_1") (pintype "passive"))
    )
    (net (code "19") (name "/DAC_CS_1") (class "Default")
      (node (ref "R34") (pin "2") (pinfunction "2_2") (pintype "passive"))
      (node (ref "R64") (pin "1") (pinfunction "1_1") (pintype "passive"))
    )
    (net (code "20") (name "/DIN") (class "Default")
      (node (ref "B1") (pin "6") (pinfunction "DIN_6") (pintype "passive"))
      (node (ref "R40") (pin "1") (pinfunction "1_1") (pintype "passive"))
      (node (ref "R55") (pin "1") (pinfunction "1_1") (pintype "passive"))
      (node (ref "R62") (pin "1") (pinfunction "1_1") (pintype "passive"))
    )
    (net (code "21") (name "/DOUT") (class "Default")
      (node (ref "B1") (pin "7") (pinfunction "DOUT_7") (pintype "passive"))
      (node (ref "R42") (pin "1") (pinfunction "1_1") (pintype "passive"))
    )
    (net (code "22") (name "/Front_Left_Res") (class "Default")
      (node (ref "C1") (pin "2") (pinfunction "2_2") (pintype "passive"))
    )
    (net (code "23") (name "/Front_Left_Speaker") (class "Default")
      (node (ref "R48") (pin "1") (pinfunction "1_1") (pintype "passive"))
    )
    (net (code "24") (name "/Front_Right_Res") (class "Default")
      (node (ref "C4") (pin "2") (pinfunction "2_2") (pintype "passive"))
    )
    (net (code "25") (name "/Front_Right_Speaker") (class "Default")
      (node (ref "R49") (pin "1") (pinfunction "1_1") (pintype "passive"))
    )
    (net (code "26") (name "/POT_CS_0") (class "Default")
      (node (ref "R22") (pin "2") (pinfunction "2_2") (pintype "passive"))
    )
    (net (code "27") (name "/POT_CS_1") (class "Default")
      (node (ref "R24") (pin "2") (pinfunction "2_2") (pintype "passive"))
    )
    (net (code "28") (name "/POT_CS_2") (class "Default")
      (node (ref "R28") (pin "2") (pinfunction "2_2") (pintype "passive"))
    )
    (net (code "29") (name "/POT_CS_3") (class "Default")
      (node (ref "R30") (pin "2") (pinfunction "2_2") (pintype "passive"))
    )
    (net (code "30") (name "/Rear_Left_Res") (class "Default")
      (node (ref "C7") (pin "2") (pinfunction "2_2") (pintype "passive"))
    )
    (net (code "31") (name "/Rear_Left_Speaker") (class "Default")
      (node (ref "R50") (pin "1") (pinfunction "1_1") (pintype "passive"))
    )
    (net (code "32") (name "/Rear_Right_Res") (class "Default")
      (node (ref "C8") (pin "2") (pinfunction "2_2") (pintype "passive"))
    )
    (net (code "33") (name "/Rear_Right_Speaker") (class "Default")
      (node (ref "R51") (pin "1") (pinfunction "1_1") (pintype "passive"))
    )
    (net (code "34") (name "/SCLK") (class "Default")
      (node (ref "B1") (pin "8") (pinfunction "SCLK_8") (pintype "passive"))
      (node (ref "R44") (pin "1") (pinfunction "1_1") (pintype "passive"))
      (node (ref "R58") (pin "1") (pinfunction "1_1") (pintype "passive"))
      (node (ref "R65") (pin "1") (pinfunction "1_1") (pintype "passive"))
    )
    (net (code "35") (name "/SRAM_CS_0") (class "Default")
      (node (ref "R35") (pin "2") (pinfunction "2_2") (pintype "passive"))
    )
    (net (code "36") (name "/SRAM_CS_1") (class "Default")
      (node (ref "R37") (pin "2") (pinfunction "2_2") (pintype "passive"))
    )
    (net (code "37") (name "/SRAM_CS_2") (class "Default")
      (node (ref "R41") (pin "2") (pinfunction "2_2") (pintype "passive"))
    )
    (net (code "38") (name "/SRAM_CS_3") (class "Default")
      (node (ref "R43") (pin "2") (pinfunction "2_2") (pintype "passive"))
    )
    (net (code "39") (name "/UPDI") (class "Default")
      (node (ref "R18") (pin "2") (pinfunction "2_2") (pintype "passive"))
      (node (ref "R2") (pin "1") (pinfunction "1_1") (pintype "passive"))
    )
    (net (code "40") (name "GND") (class "Default")
      (node (ref "B1") (pin "3") (pinfunction "GND_3") (pintype "passive"))
      (node (ref "B2") (pin "6") (pinfunction "GND_6") (pintype "passive"))
      (node (ref "B3") (pin "2") (pinfunction "ANODE_2") (pintype "passive"))
      (node (ref "B4") (pin "6") (pinfunction "GND_6") (pintype "passive"))
      (node (ref "B5") (pin "2") (pinfunction "ANODE_2") (pintype "passive"))
      (node (ref "C10") (pin "2") (pinfunction "2_2") (pintype "passive"))
      (node (ref "C11") (pin "2") (pinfunction "2_2") (pintype "passive"))
      (node (ref "C12") (pin "2") (pinfunction "2_2") (pintype "passive"))
      (node (ref "C13") (pin "2") (pinfunction "2_2") (pintype "passive"))
      (node (ref "C14") (pin "2") (pinfunction "2_2") (pintype "passive"))
      (node (ref "C2") (pin "1") (pinfunction "1_1") (pintype "passive"))
      (node (ref "C3") (pin "1") (pinfunction "1_1") (pintype "passive"))
      (node (ref "C5") (pin "1") (pinfunction "1_1") (pintype "passive"))
      (node (ref "C6") (pin "1") (pinfunction "1_1") (pintype "passive"))
      (node (ref "C9") (pin "2") (pinfunction "2_2") (pintype "passive"))
      (node (ref "H1") (pin "13") (pinfunction "13_13") (pintype "passive"))
      (node (ref "H1") (pin "15") (pinfunction "15_15") (pintype "passive"))
      (node (ref "H2") (pin "6") (pinfunction "GND_6") (pintype "passive"))
      (node (ref "H3") (pin "2") (pinfunction "2_2") (pintype "passive"))
      (node (ref "H3") (pin "4") (pinfunction "4_4") (pintype "passive"))
      (node (ref "H3") (pin "6") (pinfunction "6_6") (pintype "passive"))
      (node (ref "H3") (pin "8") (pinfunction "8_8") (pintype "passive"))
      (node (ref "IC1") (pin "19") (pinfunction "GND_1_19") (pintype "passive"))
      (node (ref "IC1") (pin "29") (pinfunction "GND_2_29") (pintype "passive"))
      (node (ref "R38") (pin "1") (pinfunction "1_1") (pintype "passive"))
      (node (ref "R39") (pin "2") (pinfunction "2_2") (pintype "passive"))
    )
    (net (code "41") (name "Net-(B1-IN1)") (class "Default")
      (node (ref "B1") (pin "5") (pinfunction "IN1_5") (pintype "passive"))
      (node (ref "R25") (pin "2") (pinfunction "2_2") (pintype "passive"))
      (node (ref "R38") (pin "2") (pinfunction "2_2") (pintype "passive"))
    )
    (net (code "42") (name "Net-(B1-IN2)") (class "Default")
      (node (ref "B1") (pin "4") (pinfunction "IN2_4") (pintype "passive"))
      (node (ref "R26") (pin "1") (pinfunction "1_1") (pintype "passive"))
      (node (ref "R39") (pin "1") (pinfunction "1_1") (pintype "passive"))
    )
    (net (code "43") (name "Net-(B2-Channel_1)") (class "Default")
      (node (ref "B2") (pin "2") (pinfunction "Channel_1_2") (pintype "passive"))
      (node (ref "R54") (pin "1") (pinfunction "1_1") (pintype "passive"))
    )
    (net (code "44") (name "Net-(B2-Channel_2)") (class "Default")
      (node (ref "B2") (pin "3") (pinfunction "Channel_2_3") (pintype "passive"))
      (node (ref "R56") (pin "1") (pinfunction "1_1") (pintype "passive"))
    )
    (net (code "45") (name "Net-(B2-DIN)") (class "Default")
      (node (ref "B2") (pin "8") (pinfunction "DIN_8") (pintype "passive"))
      (node (ref "R55") (pin "2") (pinfunction "2_2") (pintype "passive"))
    )
    (net (code "46") (name "Net-(B2-SCLK)") (class "Default")
      (node (ref "B2") (pin "10") (pinfunction "SCLK_10") (pintype "passive"))
      (node (ref "R58") (pin "2") (pinfunction "2_2") (pintype "passive"))
    )
    (net (code "47") (name "Net-(B2-VREFIN)") (class "Default")
      (node (ref "B2") (pin "7") (pinfunction "VREFIN_7") (pintype "passive"))
      (node (ref "R52") (pin "2") (pinfunction "2_2") (pintype "passive"))
    )
    (net (code "48") (name "Net-(B2-~{SYNC})") (class "Default")
      (node (ref "B2") (pin "9") (pinfunction "~{SYNC}_9") (pintype "passive"))
      (node (ref "R57") (pin "2") (pinfunction "2_2") (pintype "passive"))
    )
    (net (code "49") (name "Net-(B4-Channel_1)") (class "Default")
      (node (ref "B4") (pin "2") (pinfunction "Channel_1_2") (pintype "passive"))
      (node (ref "R61") (pin "1") (pinfunction "1_1") (pintype "passive"))
    )
    (net (code "50") (name "Net-(B4-Channel_2)") (class "Default")
      (node (ref "B4") (pin "3") (pinfunction "Channel_2_3") (pintype "passive"))
      (node (ref "R63") (pin "1") (pinfunction "1_1") (pintype "passive"))
    )
    (net (code "51") (name "Net-(B4-DIN)") (class "Default")
      (node (ref "B4") (pin "8") (pinfunction "DIN_8") (pintype "passive"))
      (node (ref "R62") (pin "2") (pinfunction "2_2") (pintype "passive"))
    )
    (net (code "52") (name "Net-(B4-SCLK)") (class "Default")
      (node (ref "B4") (pin "10") (pinfunction "SCLK_10") (pintype "passive"))
      (node (ref "R65") (pin "2") (pinfunction "2_2") (pintype "passive"))
    )
    (net (code "53") (name "Net-(B4-VREFIN)") (class "Default")
      (node (ref "B4") (pin "7") (pinfunction "VREFIN_7") (pintype "passive"))
      (node (ref "R60") (pin "2") (pinfunction "2_2") (pintype "passive"))
    )
    (net (code "54") (name "Net-(B4-~{SYNC})") (class "Default")
      (node (ref "B4") (pin "9") (pinfunction "~{SYNC}_9") (pintype "passive"))
      (node (ref "R64") (pin "2") (pinfunction "2_2") (pintype "passive"))
    )
    (net (code "55") (name "Net-(C1-Pad1)") (class "Default")
      (node (ref "C1") (pin "1") (pinfunction "1_1") (pintype "passive"))
      (node (ref "R54") (pin "2") (pinfunction "2_2") (pintype "passive"))
    )
    (net (code "56") (name "Net-(C4-Pad1)") (class "Default")
      (node (ref "C4") (pin "1") (pinfunction "1_1") (pintype "passive"))
      (node (ref "R56") (pin "2") (pinfunction "2_2") (pintype "passive"))
    )
    (net (code "57") (name "Net-(C7-Pad1)") (class "Default")
      (node (ref "C7") (pin "1") (pinfunction "1_1") (pintype "passive"))
      (node (ref "R61") (pin "2") (pinfunction "2_2") (pintype "passive"))
    )
    (net (code "58") (name "Net-(C8-Pad1)") (class "Default")
      (node (ref "C8") (pin "1") (pinfunction "1_1") (pintype "passive"))
      (node (ref "R63") (pin "2") (pinfunction "2_2") (pintype "passive"))
    )
    (net (code "59") (name "Net-(H1-Pad2)") (class "Default")
      (node (ref "H1") (pin "2") (pinfunction "2_2") (pintype "passive"))
      (node (ref "R1") (pin "2") (pinfunction "2_2") (pintype "passive"))
    )
    (net (code "60") (name "Net-(H1-Pad4)") (class "Default")
      (node (ref "H1") (pin "4") (pinfunction "4_4") (pintype "passive"))
      (node (ref "R3") (pin "2") (pinfunction "2_2") (pintype "passive"))
    )
    (net (code "61") (name "Net-(H1-Pad5)") (class "Default")
      (node (ref "H1") (pin "5") (pinfunction "5_5") (pintype "passive"))
      (node (ref "R7") (pin "1") (pinfunction "1_1") (pintype "passive"))
    )
    (net (code "62") (name "Net-(H1-Pad6)") (class "Default")
      (node (ref "H1") (pin "6") (pinfunction "6_6") (pintype "passive"))
      (node (ref "R6") (pin "2") (pinfunction "2_2") (pintype "passive"))
    )
    (net (code "63") (name "Net-(H1-Pad7)") (class "Default")
      (node (ref "H1") (pin "7") (pinfunction "7_7") (pintype "passive"))
      (node (ref "R10") (pin "1") (pinfunction "1_1") (pintype "passive"))
    )
    (net (code "64") (name "Net-(H1-Pad8)") (class "Default")
      (node (ref "H1") (pin "8") (pinfunction "8_8") (pintype "passive"))
      (node (ref "R9") (pin "2") (pinfunction "2_2") (pintype "passive"))
    )
    (net (code "65") (name "Net-(H1-Pad9)") (class "Default")
      (node (ref "H1") (pin "9") (pinfunction "9_9") (pintype "passive"))
      (node (ref "R12") (pin "1") (pinfunction "1_1") (pintype "passive"))
    )
    (net (code "66") (name "Net-(H1-Pad10)") (class "Default")
      (node (ref "H1") (pin "10") (pinfunction "10_10") (pintype "passive"))
      (node (ref "R11") (pin "2") (pinfunction "2_2") (pintype "passive"))
    )
    (net (code "67") (name "Net-(H1-Pad11)") (class "Default")
      (node (ref "H1") (pin "11") (pinfunction "11_11") (pintype "passive"))
      (node (ref "R14") (pin "1") (pinfunction "1_1") (pintype "passive"))
    )
    (net (code "68") (name "Net-(H1-Pad12)") (class "Default")
      (node (ref "H1") (pin "12") (pinfunction "12_12") (pintype "passive"))
      (node (ref "R13") (pin "2") (pinfunction "2_2") (pintype "passive"))
    )
    (net (code "69") (name "Net-(H1-Pad14)") (class "Default")
      (node (ref "H1") (pin "14") (pinfunction "14_14") (pintype "passive"))
      (node (ref "R15") (pin "2") (pinfunction "2_2") (pintype "passive"))
    )
    (net (code "70") (name "Net-(H1-Pad16)") (class "Default")
      (node (ref "H1") (pin "16") (pinfunction "16_16") (pintype "passive"))
      (node (ref "R16") (pin "2") (pinfunction "2_2") (pintype "passive"))
    )
    (net (code "71") (name "Net-(H2-NC-Pad3)") (class "Default")
      (node (ref "H2") (pin "3") (pinfunction "NC_3") (pintype "passive"))
      (node (ref "R4") (pin "2") (pinfunction "2_2") (pintype "passive"))
    )
    (net (code "72") (name "Net-(H2-NC-Pad4)") (class "Default")
      (node (ref "H2") (pin "4") (pinfunction "NC_4") (pintype "passive"))
      (node (ref "R5") (pin "1") (pinfunction "1_1") (pintype "passive"))
    )
    (net (code "73") (name "Net-(H2-NC-Pad5)") (class "Default")
      (node (ref "H2") (pin "5") (pinfunction "NC_5") (pintype "passive"))
      (node (ref "R8") (pin "2") (pinfunction "2_2") (pintype "passive"))
    )
    (net (code "74") (name "Net-(H2-UDPI)") (class "Default")
      (node (ref "H2") (pin "1") (pinfunction "UDPI_1") (pintype "passive"))
      (node (ref "R2") (pin "2") (pinfunction "2_2") (pintype "passive"))
    )
    (net (code "75") (name "Net-(H3-Pad1)") (class "Default")
      (node (ref "H3") (pin "1") (pinfunction "1_1") (pintype "passive"))
      (node (ref "R48") (pin "2") (pinfunction "2_2") (pintype "passive"))
    )
    (net (code "76") (name "Net-(H3-Pad3)") (class "Default")
      (node (ref "H3") (pin "3") (pinfunction "3_3") (pintype "passive"))
      (node (ref "R49") (pin "2") (pinfunction "2_2") (pintype "passive"))
    )
    (net (code "77") (name "Net-(H3-Pad5)") (class "Default")
      (node (ref "H3") (pin "5") (pinfunction "5_5") (pintype "passive"))
      (node (ref "R50") (pin "2") (pinfunction "2_2") (pintype "passive"))
    )
    (net (code "78") (name "Net-(H3-Pad7)") (class "Default")
      (node (ref "H3") (pin "7") (pinfunction "7_7") (pintype "passive"))
      (node (ref "R51") (pin "2") (pinfunction "2_2") (pintype "passive"))
    )
    (net (code "79") (name "Net-(IC1-PA0)") (class "Default")
      (node (ref "IC1") (pin "30") (pinfunction "PA0_30") (pintype "passive"))
      (node (ref "R17") (pin "2") (pinfunction "2_2") (pintype "passive"))
    )
    (net (code "80") (name "Net-(IC1-PA1)") (class "Default")
      (node (ref "IC1") (pin "31") (pinfunction "PA1_31") (pintype "passive"))
      (node (ref "R19") (pin "2") (pinfunction "2_2") (pintype "passive"))
    )
    (net (code "81") (name "Net-(IC1-PA2)") (class "Default")
      (node (ref "IC1") (pin "32") (pinfunction "PA2_32") (pintype "passive"))
      (node (ref "R21") (pin "2") (pinfunction "2_2") (pintype "passive"))
    )
    (net (code "82") (name "Net-(IC1-PA3)") (class "Default")
      (node (ref "IC1") (pin "1") (pinfunction "PA3_1") (pintype "passive"))
      (node (ref "R23") (pin "2") (pinfunction "2_2") (pintype "passive"))
    )
    (net (code "83") (name "Net-(IC1-PA4)") (class "Default")
      (node (ref "IC1") (pin "2") (pinfunction "PA4_2") (pintype "passive"))
      (node (ref "R27") (pin "2") (pinfunction "2_2") (pintype "passive"))
    )
    (net (code "84") (name "Net-(IC1-PA5)") (class "Default")
      (node (ref "IC1") (pin "3") (pinfunction "PA5_3") (pintype "passive"))
      (node (ref "R29") (pin "2") (pinfunction "2_2") (pintype "passive"))
    )
    (net (code "85") (name "Net-(IC1-PA6)") (class "Default")
      (node (ref "IC1") (pin "4") (pinfunction "PA6_4") (pintype "passive"))
      (node (ref "R31") (pin "2") (pinfunction "2_2") (pintype "passive"))
    )
    (net (code "86") (name "Net-(IC1-PA7)") (class "Default")
      (node (ref "IC1") (pin "5") (pinfunction "PA7_5") (pintype "passive"))
      (node (ref "R33") (pin "2") (pinfunction "2_2") (pintype "passive"))
    )
    (net (code "87") (name "Net-(IC1-PC0)") (class "Default")
      (node (ref "IC1") (pin "6") (pinfunction "PC0_6") (pintype "passive"))
      (node (ref "R36") (pin "2") (pinfunction "2_2") (pintype "passive"))
    )
    (net (code "88") (name "Net-(IC1-PC1)") (class "Default")
      (node (ref "IC1") (pin "7") (pinfunction "PC1_7") (pintype "passive"))
      (node (ref "R40") (pin "2") (pinfunction "2_2") (pintype "passive"))
    )
    (net (code "89") (name "Net-(IC1-PC2)") (class "Default")
      (node (ref "IC1") (pin "8") (pinfunction "PC2_8") (pintype "passive"))
      (node (ref "R42") (pin "2") (pinfunction "2_2") (pintype "passive"))
    )
    (net (code "90") (name "Net-(IC1-PC3)") (class "Default")
      (node (ref "IC1") (pin "9") (pinfunction "PC3_9") (pintype "passive"))
      (node (ref "R44") (pin "2") (pinfunction "2_2") (pintype "passive"))
    )
    (net (code "91") (name "Net-(IC1-PD3)") (class "Default")
      (node (ref "IC1") (pin "13") (pinfunction "PD3_13") (pintype "passive"))
      (node (ref "R45") (pin "1") (pinfunction "1_1") (pintype "passive"))
    )
    (net (code "92") (name "Net-(IC1-PD4)") (class "Default")
      (node (ref "IC1") (pin "14") (pinfunction "PD4_14") (pintype "passive"))
      (node (ref "R43") (pin "1") (pinfunction "1_1") (pintype "passive"))
    )
    (net (code "93") (name "Net-(IC1-PD5)") (class "Default")
      (node (ref "IC1") (pin "15") (pinfunction "PD5_15") (pintype "passive"))
      (node (ref "R41") (pin "1") (pinfunction "1_1") (pintype "passive"))
    )
    (net (code "94") (name "Net-(IC1-PD6)") (class "Default")
      (node (ref "IC1") (pin "16") (pinfunction "PD6_16") (pintype "passive"))
      (node (ref "R37") (pin "1") (pinfunction "1_1") (pintype "passive"))
    )
    (net (code "95") (name "Net-(IC1-PD7)") (class "Default")
      (node (ref "IC1") (pin "17") (pinfunction "PD7_17") (pintype "passive"))
      (node (ref "R35") (pin "1") (pinfunction "1_1") (pintype "passive"))
    )
    (net (code "96") (name "Net-(IC1-PD~{1})") (class "Default")
      (node (ref "IC1") (pin "11") (pinfunction "PD~{1}_11") (pintype "passive"))
      (node (ref "R47") (pin "1") (pinfunction "1_1") (pintype "passive"))
    )
    (net (code "97") (name "Net-(IC1-PD~{2})") (class "Default")
      (node (ref "IC1") (pin "12") (pinfunction "PD~{2}_12") (pintype "passive"))
      (node (ref "R46") (pin "1") (pinfunction "1_1") (pintype "passive"))
    )
    (net (code "98") (name "Net-(IC1-PF0)") (class "Default")
      (node (ref "IC1") (pin "20") (pinfunction "PF0_20") (pintype "passive"))
      (node (ref "R34") (pin "1") (pinfunction "1_1") (pintype "passive"))
    )
    (net (code "99") (name "Net-(IC1-PF1)") (class "Default")
      (node (ref "IC1") (pin "21") (pinfunction "PF1_21") (pintype "passive"))
      (node (ref "R32") (pin "1") (pinfunction "1_1") (pintype "passive"))
    )
    (net (code "100") (name "Net-(IC1-PF2)") (class "Default")
      (node (ref "IC1") (pin "22") (pinfunction "PF2_22") (pintype "passive"))
      (node (ref "R30") (pin "1") (pinfunction "1_1") (pintype "passive"))
    )
    (net (code "101") (name "Net-(IC1-PF3)") (class "Default")
      (node (ref "IC1") (pin "23") (pinfunction "PF3_23") (pintype "passive"))
      (node (ref "R28") (pin "1") (pinfunction "1_1") (pintype "passive"))
    )
    (net (code "102") (name "Net-(IC1-PF4)") (class "Default")
      (node (ref "IC1") (pin "24") (pinfunction "PF4_24") (pintype "passive"))
      (node (ref "R24") (pin "1") (pinfunction "1_1") (pintype "passive"))
    )
    (net (code "103") (name "Net-(IC1-PF5)") (class "Default")
      (node (ref "IC1") (pin "25") (pinfunction "PF5_25") (pintype "passive"))
      (node (ref "R22") (pin "1") (pinfunction "1_1") (pintype "passive"))
    )
    (net (code "104") (name "Net-(IC1-PF6_(~{RESET)})") (class "Default")
      (node (ref "IC1") (pin "26") (pinfunction "PF6_(~{RESET)}_26") (pintype "passive"))
      (node (ref "R20") (pin "1") (pinfunction "1_1") (pintype "passive"))
    )
    (net (code "105") (name "Net-(IC1-PF7_(UPDI))") (class "Default")
      (node (ref "IC1") (pin "27") (pinfunction "PF7_(UPDI)_27") (pintype "passive"))
      (node (ref "R18") (pin "1") (pinfunction "1_1") (pintype "passive"))
    )
    (net (code "106") (name "Net-(R4-Pad1)") (class "Default")
      (node (ref "R4") (pin "1") (pinfunction "1_1") (pintype "passive"))
      (node (ref "TP2") (pin "1") (pinfunction "1_1") (pintype "passive"))
    )
    (net (code "107") (name "Net-(R5-Pad2)") (class "Default")
      (node (ref "R5") (pin "2") (pinfunction "2_2") (pintype "passive"))
      (node (ref "TP3") (pin "1") (pinfunction "1_1") (pintype "passive"))
    )
    (net (code "108") (name "Net-(R8-Pad1)") (class "Default")
      (node (ref "R8") (pin "1") (pinfunction "1_1") (pintype "passive"))
      (node (ref "TP4") (pin "1") (pinfunction "1_1") (pintype "passive"))
    )
    (net (code "109") (name "unconnected-(B2-NC_1-Pad4)") (class "Default")
      (node (ref "B2") (pin "4") (pinfunction "NC_1_4") (pintype "passive+no_connect"))
    )
    (net (code "110") (name "unconnected-(B2-NC_2-Pad5)") (class "Default")
      (node (ref "B2") (pin "5") (pinfunction "NC_2_5") (pintype "passive+no_connect"))
    )
    (net (code "111") (name "unconnected-(B3-NC-Pad3)") (class "Default")
      (node (ref "B3") (pin "3") (pinfunction "NC_3") (pintype "passive+no_connect"))
    )
    (net (code "112") (name "unconnected-(B4-NC_1-Pad4)") (class "Default")
      (node (ref "B4") (pin "4") (pinfunction "NC_1_4") (pintype "passive+no_connect"))
    )
    (net (code "113") (name "unconnected-(B4-NC_2-Pad5)") (class "Default")
      (node (ref "B4") (pin "5") (pinfunction "NC_2_5") (pintype "passive+no_connect"))
    )
    (net (code "114") (name "unconnected-(B5-NC-Pad3)") (class "Default")
      (node (ref "B5") (pin "3") (pinfunction "NC_3") (pintype "passive+no_connect"))
    )
  )
)
